# piezo-preamp-tickler_V0-9a.net
KiCad netlist of a schematic drawn in EAGLE
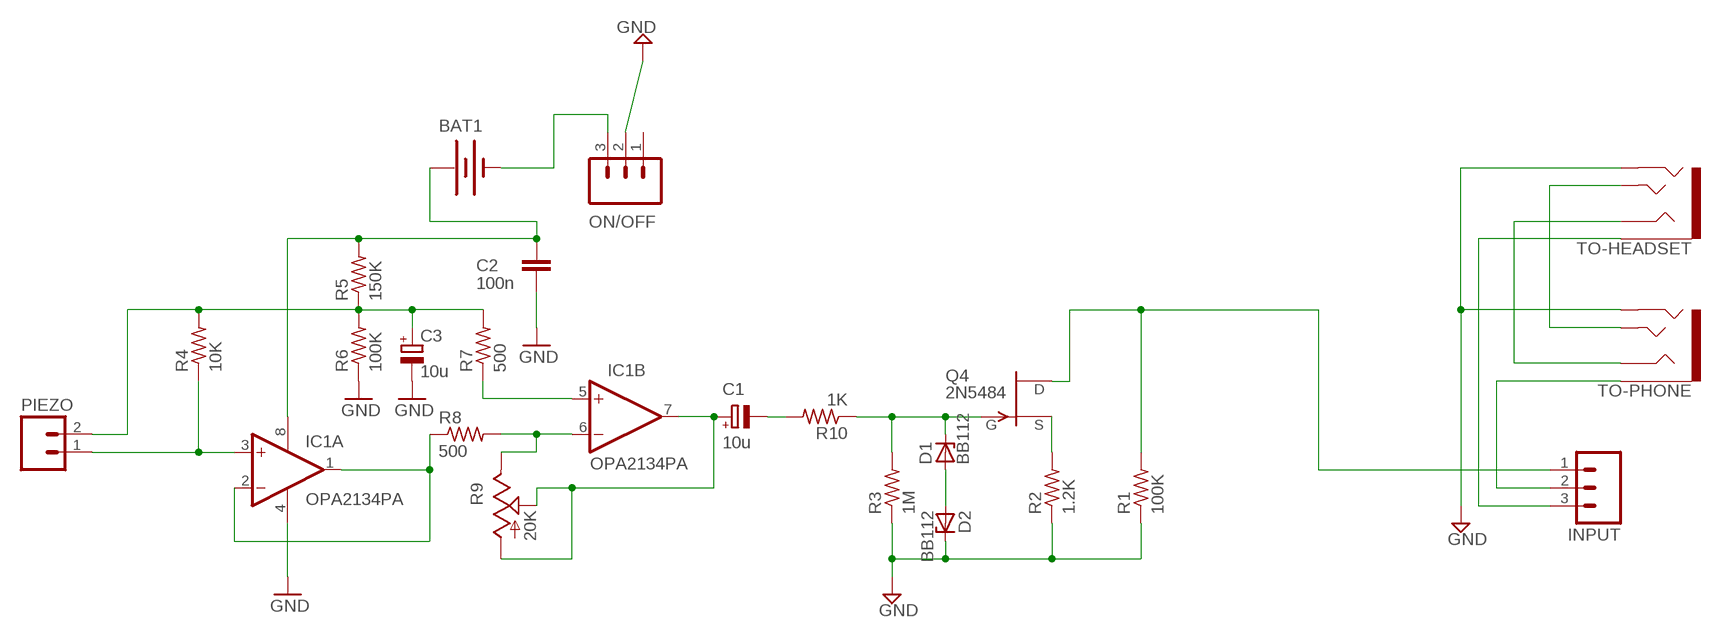
[diagram p0: schematic, sheet 1]

(export (version "E")
  (design (tool "Eeschema 10.0.6"))
  (components
    (comp (ref "BAT1")
      (value "BATTERYA23")
      (footprint "eagle-import:BATTERY-A23")
      (libsource (lib "eagle-import") (part "BATTERYA23"))
    )
    (comp (ref "C1")
      (value "10u")
      (footprint "eagle-import:E2,5-5")
      (libsource (lib "eagle-import") (part "CPOL-EUE2.5-5"))
    )
    (comp (ref "C2")
      (value "100n")
      (footprint "eagle-import:C025-025X050")
      (libsource (lib "eagle-import") (part "C-EU025-025X050"))
    )
    (comp (ref "C3")
      (value "10u")
      (footprint "eagle-import:E2,5-5")
      (libsource (lib "eagle-import") (part "CPOL-EUE2.5-5"))
    )
    (comp (ref "D1")
      (value "BB112")
      (footprint "eagle-import:ZDIO-2.5")
      (libsource (lib "eagle-import") (part "ZENER-DIODEZD-2.5"))
    )
    (comp (ref "D2")
      (value "BB112")
      (footprint "eagle-import:ZDIO-2.5")
      (libsource (lib "eagle-import") (part "ZENER-DIODEZD-2.5"))
    )
    (comp (ref "IC1")
      (value "OPA2134PA")
      (footprint "eagle-import:DIL08")
      (libsource (lib "eagle-import") (part "OPA2PA134"))
    )
    (comp (ref "INPUT")
      (value "M03SINGLE-POLE-DOUBLE-THROW")
      (footprint "eagle-import:SPDT-SWITCH")
      (libsource (lib "eagle-import") (part "M03SINGLE-POLE-DOUBLE-THROW"))
    )
    (comp (ref "ON/OFF")
      (value "labl")
      (footprint "eagle-import:SPDT-SWITCH")
      (libsource (lib "eagle-import") (part "M03SINGLE-POLE-DOUBLE-THROW"))
    )
    (comp (ref "PIEZO")
      (value "M02LOCK")
      (footprint "eagle-import:1X02_LOCK")
      (libsource (lib "eagle-import") (part "M02LOCK"))
    )
    (comp (ref "Q4")
      (value "2N5484")
      (footprint "eagle-import:TO92-")
      (libsource (lib "eagle-import") (part "?5482N4"))
    )
    (comp (ref "R1")
      (value "100K")
      (footprint "eagle-import:0204V")
      (libsource (lib "eagle-import") (part "R-US_0204/2V"))
    )
    (comp (ref "R2")
      (value "1.2K")
      (footprint "eagle-import:0204V")
      (libsource (lib "eagle-import") (part "R-US_0204/2V"))
    )
    (comp (ref "R3")
      (value "1M")
      (footprint "eagle-import:0204V")
      (libsource (lib "eagle-import") (part "R-US_0204/2V"))
    )
    (comp (ref "R4")
      (value "10K")
      (footprint "eagle-import:0204V")
      (libsource (lib "eagle-import") (part "R-US_0204/2V"))
    )
    (comp (ref "R5")
      (value "150K")
      (footprint "eagle-import:0204V")
      (libsource (lib "eagle-import") (part "R-US_0204/2V"))
    )
    (comp (ref "R6")
      (value "100K")
      (footprint "eagle-import:0204V")
      (libsource (lib "eagle-import") (part "R-US_0204/2V"))
    )
    (comp (ref "R7")
      (value "500")
      (footprint "eagle-import:0204V")
      (libsource (lib "eagle-import") (part "R-US_0204/2V"))
    )
    (comp (ref "R8")
      (value "500")
      (footprint "eagle-import:0204V")
      (libsource (lib "eagle-import") (part "R-US_0204/2V"))
    )
    (comp (ref "R9")
      (value "20K")
      (footprint "eagle-import:BOURNS-TRIMPOT-3309W1")
      (fields (field (name "THIS") "20K"))
      (libsource (lib "eagle-import") (part "TRIMPOT-BOURNS"))
    )
    (comp (ref "R10")
      (value "1K")
      (footprint "eagle-import:0204V")
      (libsource (lib "eagle-import") (part "R-US_0204/2V"))
    )
    (comp (ref "TO-HEADSET")
      (value "AUDIO-JACK3LGPADS")
      (footprint "eagle-import:AUDIO-JACK-TRRS-SMD")
      (libsource (lib "eagle-import") (part "AUDIO-JACK3LGPADS"))
    )
    (comp (ref "TO-PHONE")
      (value "AUDIO-JACK3LGPADS")
      (footprint "eagle-import:AUDIO-JACK-TRRS-SMD")
      (libsource (lib "eagle-import") (part "AUDIO-JACK3LGPADS"))
    )
  )
  (nets
    (net (code "1") (name "GND") (class "Default")
      (node (ref "C2") (pin "1") (pinfunction "1_1") (pintype "passive"))
      (node (ref "C3") (pin "-") (pinfunction "-_-") (pintype "passive"))
      (node (ref "D2") (pin "C") (pinfunction "C_C") (pintype "passive"))
      (node (ref "IC1") (pin "4") (pinfunction "V-_4") (pintype "power_in"))
      (node (ref "ON/OFF") (pin "2") (pinfunction "2_2") (pintype "passive"))
      (node (ref "R1") (pin "1") (pinfunction "1_1") (pintype "passive"))
      (node (ref "R2") (pin "1") (pinfunction "1_1") (pintype "passive"))
      (node (ref "R3") (pin "1") (pinfunction "1_1") (pintype "passive"))
      (node (ref "R6") (pin "1") (pinfunction "1_1") (pintype "passive"))
      (node (ref "TO-HEADSET") (pin "RING2") (pinfunction "RING2_RING2") (pintype "bidirectional"))
      (node (ref "TO-PHONE") (pin "RING2") (pinfunction "RING2_RING2") (pintype "bidirectional"))
    )
    (net (code "2") (name "Net-(BAT1-+)") (class "Default")
      (node (ref "BAT1") (pin "PWR@1") (pinfunction "+_PWR@1") (pintype "power_in"))
      (node (ref "C2") (pin "2") (pinfunction "2_2") (pintype "passive"))
      (node (ref "IC1") (pin "8") (pinfunction "V+_8") (pintype "power_in"))
      (node (ref "R5") (pin "2") (pinfunction "2_2") (pintype "passive"))
    )
    (net (code "3") (name "Net-(BAT1--)") (class "Default")
      (node (ref "BAT1") (pin "GND@1") (pinfunction "-_GND@1") (pintype "power_in"))
      (node (ref "ON/OFF") (pin "3") (pinfunction "3_3") (pintype "passive"))
    )
    (net (code "4") (name "Net-(C1-Pad-)") (class "Default")
      (node (ref "C1") (pin "-") (pinfunction "-_-") (pintype "passive"))
      (node (ref "R10") (pin "2") (pinfunction "2_2") (pintype "passive"))
    )
    (net (code "5") (name "Net-(C3-Pad+)") (class "Default")
      (node (ref "C3") (pin "+") (pinfunction "+_+") (pintype "passive"))
      (node (ref "PIEZO") (pin "2") (pinfunction "2_2") (pintype "passive"))
      (node (ref "R4") (pin "2") (pinfunction "2_2") (pintype "passive"))
      (node (ref "R5") (pin "1") (pinfunction "1_1") (pintype "passive"))
      (node (ref "R6") (pin "2") (pinfunction "2_2") (pintype "passive"))
      (node (ref "R7") (pin "2") (pinfunction "2_2") (pintype "passive"))
    )
    (net (code "6") (name "Net-(D1-PadA)") (class "Default")
      (node (ref "D1") (pin "A") (pinfunction "A_A") (pintype "passive"))
      (node (ref "D2") (pin "A") (pinfunction "A_A") (pintype "passive"))
    )
    (net (code "7") (name "Net-(IC1A-+IN)") (class "Default")
      (node (ref "IC1") (pin "3") (pinfunction "+IN_3") (pintype "input"))
      (node (ref "PIEZO") (pin "1") (pinfunction "1_1") (pintype "passive"))
      (node (ref "R4") (pin "1") (pinfunction "1_1") (pintype "passive"))
    )
    (net (code "8") (name "Net-(IC1A--IN)") (class "Default")
      (node (ref "IC1") (pin "1") (pinfunction "OUT_1") (pintype "output"))
      (node (ref "IC1") (pin "2") (pinfunction "-IN_2") (pintype "input"))
      (node (ref "R8") (pin "1") (pinfunction "1_1") (pintype "passive"))
    )
    (net (code "9") (name "Net-(IC1B-+IN)") (class "Default")
      (node (ref "IC1") (pin "5") (pinfunction "+IN_5") (pintype "input"))
      (node (ref "R7") (pin "1") (pinfunction "1_1") (pintype "passive"))
    )
    (net (code "10") (name "Net-(IC1B--IN)") (class "Default")
      (node (ref "IC1") (pin "6") (pinfunction "-IN_6") (pintype "input"))
      (node (ref "R8") (pin "2") (pinfunction "2_2") (pintype "passive"))
      (node (ref "R9") (pin "P$3") (pinfunction "OUT_P$3") (pintype "passive"))
    )
    (net (code "11") (name "Net-(IC1B-OUT)") (class "Default")
      (node (ref "C1") (pin "+") (pinfunction "+_+") (pintype "passive"))
      (node (ref "IC1") (pin "7") (pinfunction "OUT_7") (pintype "output"))
      (node (ref "R9") (pin "P$1") (pinfunction "IN_P$1") (pintype "passive"))
      (node (ref "R9") (pin "P$2") (pinfunction "WIPER_P$2") (pintype "passive"))
    )
    (net (code "12") (name "Net-(INPUT-Pad2)") (class "Default")
      (node (ref "INPUT") (pin "2") (pinfunction "2_2") (pintype "passive"))
      (node (ref "TO-PHONE") (pin "EARTH") (pinfunction "EARTH_EARTH") (pintype "bidirectional"))
    )
    (net (code "13") (name "Net-(INPUT-Pad3)") (class "Default")
      (node (ref "INPUT") (pin "3") (pinfunction "3_3") (pintype "passive"))
      (node (ref "TO-HEADSET") (pin "EARTH") (pinfunction "EARTH_EARTH") (pintype "bidirectional"))
    )
    (net (code "14") (name "Net-(Q4-D)") (class "Default")
      (node (ref "INPUT") (pin "1") (pinfunction "1_1") (pintype "passive"))
      (node (ref "Q4") (pin "3") (pinfunction "D_3") (pintype "passive"))
      (node (ref "R1") (pin "2") (pinfunction "2_2") (pintype "passive"))
    )
    (net (code "15") (name "Net-(Q4-G)") (class "Default")
      (node (ref "D1") (pin "C") (pinfunction "C_C") (pintype "passive"))
      (node (ref "Q4") (pin "1") (pinfunction "G_1") (pintype "passive"))
      (node (ref "R10") (pin "1") (pinfunction "1_1") (pintype "passive"))
      (node (ref "R3") (pin "2") (pinfunction "2_2") (pintype "passive"))
    )
    (net (code "16") (name "Net-(Q4-S)") (class "Default")
      (node (ref "Q4") (pin "2") (pinfunction "S_2") (pintype "passive"))
      (node (ref "R2") (pin "2") (pinfunction "2_2") (pintype "passive"))
    )
    (net (code "17") (name "Net-(TO-HEADSET-PadRING1)") (class "Default")
      (node (ref "TO-HEADSET") (pin "RING1") (pinfunction "RING1_RING1") (pintype "bidirectional"))
      (node (ref "TO-PHONE") (pin "RING1") (pinfunction "RING1_RING1") (pintype "bidirectional"))
    )
    (net (code "18") (name "Net-(TO-HEADSET-PadTIP)") (class "Default")
      (node (ref "TO-HEADSET") (pin "TIP") (pinfunction "TIP_TIP") (pintype "bidirectional"))
      (node (ref "TO-PHONE") (pin "TIP") (pinfunction "TIP_TIP") (pintype "bidirectional"))
    )
    (net (code "19") (name "unconnected-(ON/OFF-Pad1)") (class "Default")
      (node (ref "ON/OFF") (pin "1") (pinfunction "1_1") (pintype "passive"))
    )
  )
)
